# P3DA.net
KiCad netlist of a schematic drawn in EAGLE
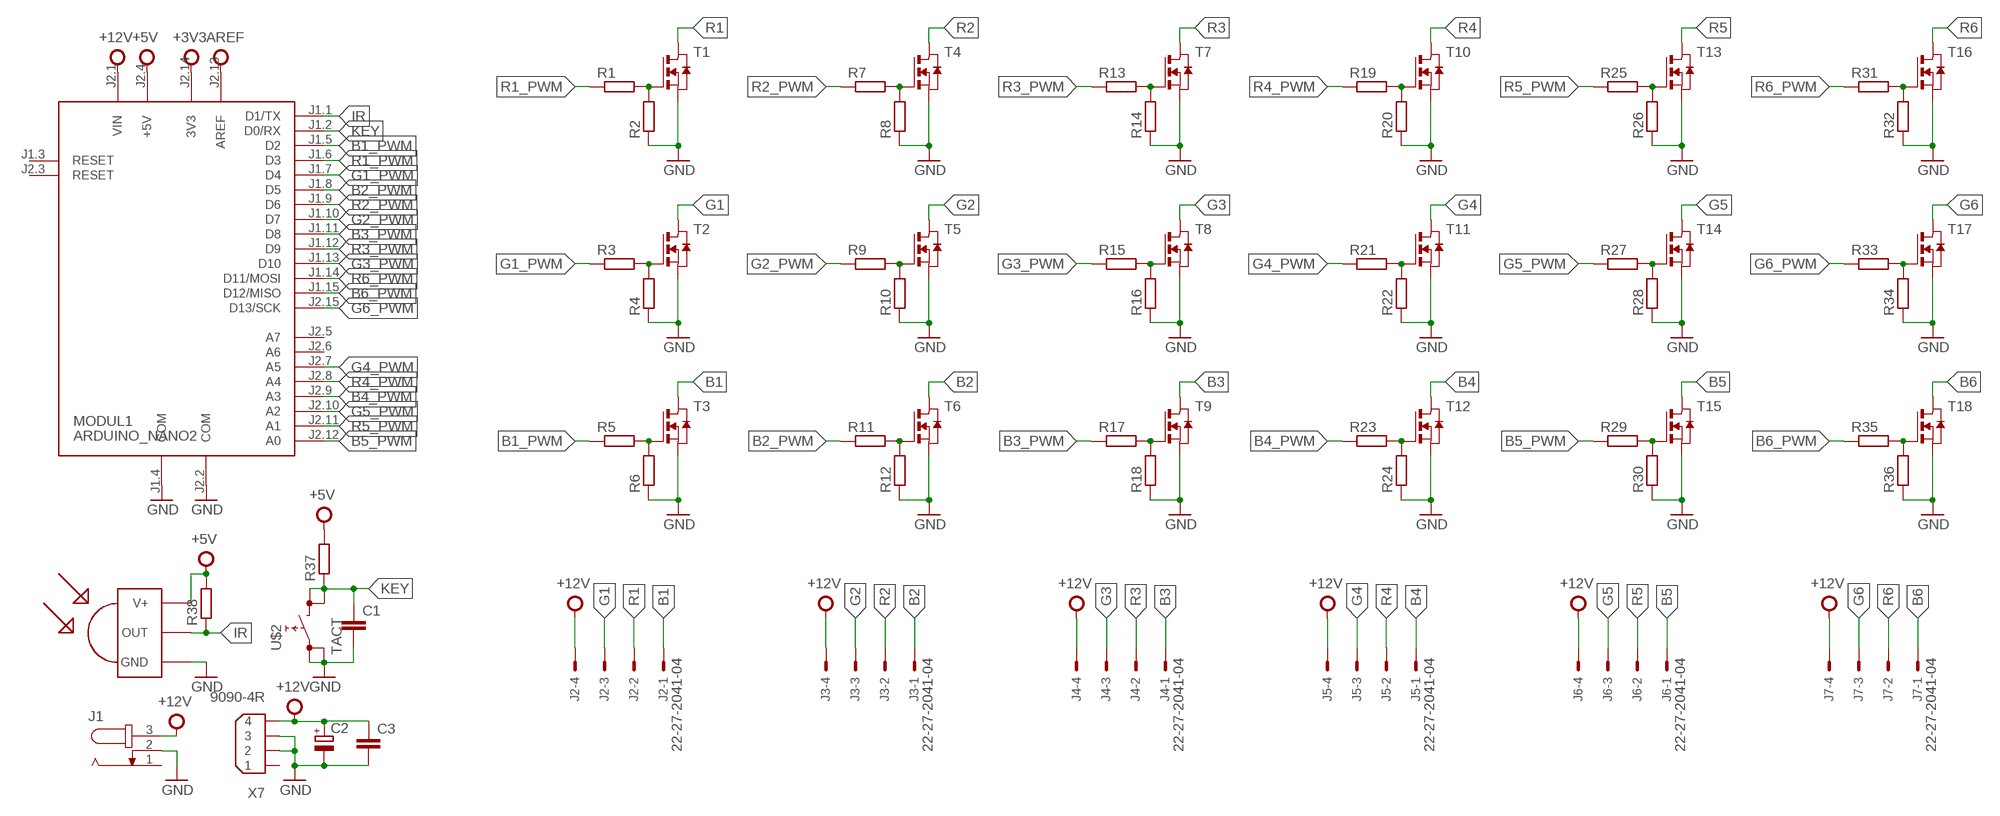
[diagram p0: schematic, sheet 1]

(export (version "E")
  (design (tool "Eeschema 10.0.6"))
  (components
    (comp (ref "C1")
      (value "C-EUC0805")
      (footprint "eagle-import:C0805")
      (libsource (lib "eagle-import") (part "C-EUC0805"))
    )
    (comp (ref "C2")
      (value "CPOL-EUE5-13")
      (footprint "eagle-import:E5-13")
      (libsource (lib "eagle-import") (part "CPOL-EUE5-13"))
    )
    (comp (ref "C3")
      (value "C-EUC1206")
      (footprint "eagle-import:C1206")
      (libsource (lib "eagle-import") (part "C-EUC1206"))
    )
    (comp (ref "J1")
      (value "JACK-PLUG1")
      (footprint "eagle-import:SPC4078")
      (libsource (lib "eagle-import") (part "JACK-PLUG1"))
    )
    (comp (ref "J2")
      (value "22-27-2041-04")
      (footprint "eagle-import:6410-04")
      (libsource (lib "eagle-import") (part "22-?-0427-2041"))
    )
    (comp (ref "J3")
      (value "22-27-2041-04")
      (footprint "eagle-import:6410-04")
      (libsource (lib "eagle-import") (part "22-?-0427-2041"))
    )
    (comp (ref "J4")
      (value "22-27-2041-04")
      (footprint "eagle-import:6410-04")
      (libsource (lib "eagle-import") (part "22-?-0427-2041"))
    )
    (comp (ref "J5")
      (value "22-27-2041-04")
      (footprint "eagle-import:6410-04")
      (libsource (lib "eagle-import") (part "22-?-0427-2041"))
    )
    (comp (ref "J6")
      (value "22-27-2041-04")
      (footprint "eagle-import:6410-04")
      (libsource (lib "eagle-import") (part "22-?-0427-2041"))
    )
    (comp (ref "J7")
      (value "22-27-2041-04")
      (footprint "eagle-import:6410-04")
      (libsource (lib "eagle-import") (part "22-?-0427-2041"))
    )
    (comp (ref "MODUL1")
      (value "ARDUINO_NANO2")
      (footprint "eagle-import:ARDUINO_NANO2")
      (libsource (lib "eagle-import") (part "ARDUINO_NANO2"))
    )
    (comp (ref "R1")
      (value "R-EU_R0805")
      (footprint "eagle-import:R0805")
      (libsource (lib "eagle-import") (part "R-EU_R0805"))
    )
    (comp (ref "R2")
      (value "R-EU_R0805")
      (footprint "eagle-import:R0805")
      (libsource (lib "eagle-import") (part "R-EU_R0805"))
    )
    (comp (ref "R3")
      (value "R-EU_R0805")
      (footprint "eagle-import:R0805")
      (libsource (lib "eagle-import") (part "R-EU_R0805"))
    )
    (comp (ref "R4")
      (value "R-EU_R0805")
      (footprint "eagle-import:R0805")
      (libsource (lib "eagle-import") (part "R-EU_R0805"))
    )
    (comp (ref "R5")
      (value "R-EU_R0805")
      (footprint "eagle-import:R0805")
      (libsource (lib "eagle-import") (part "R-EU_R0805"))
    )
    (comp (ref "R6")
      (value "R-EU_R0805")
      (footprint "eagle-import:R0805")
      (libsource (lib "eagle-import") (part "R-EU_R0805"))
    )
    (comp (ref "R7")
      (value "R-EU_R0805")
      (footprint "eagle-import:R0805")
      (libsource (lib "eagle-import") (part "R-EU_R0805"))
    )
    (comp (ref "R8")
      (value "R-EU_R0805")
      (footprint "eagle-import:R0805")
      (libsource (lib "eagle-import") (part "R-EU_R0805"))
    )
    (comp (ref "R9")
      (value "R-EU_R0805")
      (footprint "eagle-import:R0805")
      (libsource (lib "eagle-import") (part "R-EU_R0805"))
    )
    (comp (ref "R10")
      (value "R-EU_R0805")
      (footprint "eagle-import:R0805")
      (libsource (lib "eagle-import") (part "R-EU_R0805"))
    )
    (comp (ref "R11")
      (value "R-EU_R0805")
      (footprint "eagle-import:R0805")
      (libsource (lib "eagle-import") (part "R-EU_R0805"))
    )
    (comp (ref "R12")
      (value "R-EU_R0805")
      (footprint "eagle-import:R0805")
      (libsource (lib "eagle-import") (part "R-EU_R0805"))
    )
    (comp (ref "R13")
      (value "R-EU_R0805")
      (footprint "eagle-import:R0805")
      (libsource (lib "eagle-import") (part "R-EU_R0805"))
    )
    (comp (ref "R14")
      (value "R-EU_R0805")
      (footprint "eagle-import:R0805")
      (libsource (lib "eagle-import") (part "R-EU_R0805"))
    )
    (comp (ref "R15")
      (value "R-EU_R0805")
      (footprint "eagle-import:R0805")
      (libsource (lib "eagle-import") (part "R-EU_R0805"))
    )
    (comp (ref "R16")
      (value "R-EU_R0805")
      (footprint "eagle-import:R0805")
      (libsource (lib "eagle-import") (part "R-EU_R0805"))
    )
    (comp (ref "R17")
      (value "R-EU_R0805")
      (footprint "eagle-import:R0805")
      (libsource (lib "eagle-import") (part "R-EU_R0805"))
    )
    (comp (ref "R18")
      (value "R-EU_R0805")
      (footprint "eagle-import:R0805")
      (libsource (lib "eagle-import") (part "R-EU_R0805"))
    )
    (comp (ref "R19")
      (value "R-EU_R0805")
      (footprint "eagle-import:R0805")
      (libsource (lib "eagle-import") (part "R-EU_R0805"))
    )
    (comp (ref "R20")
      (value "R-EU_R0805")
      (footprint "eagle-import:R0805")
      (libsource (lib "eagle-import") (part "R-EU_R0805"))
    )
    (comp (ref "R21")
      (value "R-EU_R0805")
      (footprint "eagle-import:R0805")
      (libsource (lib "eagle-import") (part "R-EU_R0805"))
    )
    (comp (ref "R22")
      (value "R-EU_R0805")
      (footprint "eagle-import:R0805")
      (libsource (lib "eagle-import") (part "R-EU_R0805"))
    )
    (comp (ref "R23")
      (value "R-EU_R0805")
      (footprint "eagle-import:R0805")
      (libsource (lib "eagle-import") (part "R-EU_R0805"))
    )
    (comp (ref "R24")
      (value "R-EU_R0805")
      (footprint "eagle-import:R0805")
      (libsource (lib "eagle-import") (part "R-EU_R0805"))
    )
    (comp (ref "R25")
      (value "R-EU_R0805")
      (footprint "eagle-import:R0805")
      (libsource (lib "eagle-import") (part "R-EU_R0805"))
    )
    (comp (ref "R26")
      (value "R-EU_R0805")
      (footprint "eagle-import:R0805")
      (libsource (lib "eagle-import") (part "R-EU_R0805"))
    )
    (comp (ref "R27")
      (value "R-EU_R0805")
      (footprint "eagle-import:R0805")
      (libsource (lib "eagle-import") (part "R-EU_R0805"))
    )
    (comp (ref "R28")
      (value "R-EU_R0805")
      (footprint "eagle-import:R0805")
      (libsource (lib "eagle-import") (part "R-EU_R0805"))
    )
    (comp (ref "R29")
      (value "R-EU_R0805")
      (footprint "eagle-import:R0805")
      (libsource (lib "eagle-import") (part "R-EU_R0805"))
    )
    (comp (ref "R30")
      (value "R-EU_R0805")
      (footprint "eagle-import:R0805")
      (libsource (lib "eagle-import") (part "R-EU_R0805"))
    )
    (comp (ref "R31")
      (value "R-EU_R0805")
      (footprint "eagle-import:R0805")
      (libsource (lib "eagle-import") (part "R-EU_R0805"))
    )
    (comp (ref "R32")
      (value "R-EU_R0805")
      (footprint "eagle-import:R0805")
      (libsource (lib "eagle-import") (part "R-EU_R0805"))
    )
    (comp (ref "R33")
      (value "R-EU_R0805")
      (footprint "eagle-import:R0805")
      (libsource (lib "eagle-import") (part "R-EU_R0805"))
    )
    (comp (ref "R34")
      (value "R-EU_R0805")
      (footprint "eagle-import:R0805")
      (libsource (lib "eagle-import") (part "R-EU_R0805"))
    )
    (comp (ref "R35")
      (value "R-EU_R0805")
      (footprint "eagle-import:R0805")
      (libsource (lib "eagle-import") (part "R-EU_R0805"))
    )
    (comp (ref "R36")
      (value "R-EU_R0805")
      (footprint "eagle-import:R0805")
      (libsource (lib "eagle-import") (part "R-EU_R0805"))
    )
    (comp (ref "R37")
      (value "R-EU_R0805")
      (footprint "eagle-import:R0805")
      (libsource (lib "eagle-import") (part "R-EU_R0805"))
    )
    (comp (ref "R38")
      (value "R-EU_R0805")
      (footprint "eagle-import:R0805")
      (libsource (lib "eagle-import") (part "R-EU_R0805"))
    )
    (comp (ref "T1")
      (value "NMOSSOT23")
      (footprint "eagle-import:SOT-23")
      (libsource (lib "eagle-import") (part "NMOSSOT23"))
    )
    (comp (ref "T2")
      (value "NMOSSOT23")
      (footprint "eagle-import:SOT-23")
      (libsource (lib "eagle-import") (part "NMOSSOT23"))
    )
    (comp (ref "T3")
      (value "NMOSSOT23")
      (footprint "eagle-import:SOT-23")
      (libsource (lib "eagle-import") (part "NMOSSOT23"))
    )
    (comp (ref "T4")
      (value "NMOSSOT23")
      (footprint "eagle-import:SOT-23")
      (libsource (lib "eagle-import") (part "NMOSSOT23"))
    )
    (comp (ref "T5")
      (value "NMOSSOT23")
      (footprint "eagle-import:SOT-23")
      (libsource (lib "eagle-import") (part "NMOSSOT23"))
    )
    (comp (ref "T6")
      (value "NMOSSOT23")
      (footprint "eagle-import:SOT-23")
      (libsource (lib "eagle-import") (part "NMOSSOT23"))
    )
    (comp (ref "T7")
      (value "NMOSSOT23")
      (footprint "eagle-import:SOT-23")
      (libsource (lib "eagle-import") (part "NMOSSOT23"))
    )
    (comp (ref "T8")
      (value "NMOSSOT23")
      (footprint "eagle-import:SOT-23")
      (libsource (lib "eagle-import") (part "NMOSSOT23"))
    )
    (comp (ref "T9")
      (value "NMOSSOT23")
      (footprint "eagle-import:SOT-23")
      (libsource (lib "eagle-import") (part "NMOSSOT23"))
    )
    (comp (ref "T10")
      (value "NMOSSOT23")
      (footprint "eagle-import:SOT-23")
      (libsource (lib "eagle-import") (part "NMOSSOT23"))
    )
    (comp (ref "T11")
      (value "NMOSSOT23")
      (footprint "eagle-import:SOT-23")
      (libsource (lib "eagle-import") (part "NMOSSOT23"))
    )
    (comp (ref "T12")
      (value "NMOSSOT23")
      (footprint "eagle-import:SOT-23")
      (libsource (lib "eagle-import") (part "NMOSSOT23"))
    )
    (comp (ref "T13")
      (value "NMOSSOT23")
      (footprint "eagle-import:SOT-23")
      (libsource (lib "eagle-import") (part "NMOSSOT23"))
    )
    (comp (ref "T14")
      (value "NMOSSOT23")
      (footprint "eagle-import:SOT-23")
      (libsource (lib "eagle-import") (part "NMOSSOT23"))
    )
    (comp (ref "T15")
      (value "NMOSSOT23")
      (footprint "eagle-import:SOT-23")
      (libsource (lib "eagle-import") (part "NMOSSOT23"))
    )
    (comp (ref "T16")
      (value "NMOSSOT23")
      (footprint "eagle-import:SOT-23")
      (libsource (lib "eagle-import") (part "NMOSSOT23"))
    )
    (comp (ref "T17")
      (value "NMOSSOT23")
      (footprint "eagle-import:SOT-23")
      (libsource (lib "eagle-import") (part "NMOSSOT23"))
    )
    (comp (ref "T18")
      (value "NMOSSOT23")
      (footprint "eagle-import:SOT-23")
      (libsource (lib "eagle-import") (part "NMOSSOT23"))
    )
    (comp (ref "U$1")
      (value "TSOP1738")
      (footprint "eagle-import:TSOP17XX")
      (libsource (lib "eagle-import") (part "TSOP1738"))
    )
    (comp (ref "U$2")
      (value "TACT")
      (footprint "eagle-import:TL1105")
      (libsource (lib "eagle-import") (part "TACT"))
    )
    (comp (ref "X7")
      (value "9090-4R")
      (footprint "eagle-import:9090-4R")
      (libsource (lib "eagle-import") (part "9090-4R"))
    )
  )
  (nets
    (net (code "1") (name "+3V3") (class "Default")
      (node (ref "MODUL1") (pin "J2.14") (pinfunction "3V3_J2.14") (pintype "power_in"))
    )
    (net (code "2") (name "+5V") (class "Default")
      (node (ref "MODUL1") (pin "J2.4") (pinfunction "+5V_J2.4") (pintype "power_in"))
      (node (ref "R37") (pin "2") (pinfunction "2_2") (pintype "passive"))
      (node (ref "R38") (pin "2") (pinfunction "2_2") (pintype "passive"))
      (node (ref "U$1") (pin "V+") (pinfunction "V+_V+") (pintype "bidirectional"))
    )
    (net (code "3") (name "+12V") (class "Default")
      (node (ref "C2") (pin "+") (pinfunction "+_+") (pintype "passive"))
      (node (ref "C3") (pin "1") (pinfunction "1_1") (pintype "passive"))
      (node (ref "J1") (pin "3") (pinfunction "3_3") (pintype "passive"))
      (node (ref "J2") (pin "4") (pinfunction "S_4") (pintype "passive"))
      (node (ref "J3") (pin "4") (pinfunction "S_4") (pintype "passive"))
      (node (ref "J4") (pin "4") (pinfunction "S_4") (pintype "passive"))
      (node (ref "J5") (pin "4") (pinfunction "S_4") (pintype "passive"))
      (node (ref "J6") (pin "4") (pinfunction "S_4") (pintype "passive"))
      (node (ref "J7") (pin "4") (pinfunction "S_4") (pintype "passive"))
      (node (ref "MODUL1") (pin "J2.1") (pinfunction "VIN_J2.1") (pintype "power_in"))
      (node (ref "X7") (pin "4") (pinfunction "4_4") (pintype "passive"))
    )
    (net (code "4") (name "AREF") (class "Default")
      (node (ref "MODUL1") (pin "J2.13") (pinfunction "AREF_J2.13") (pintype "power_in"))
    )
    (net (code "5") (name "B1") (class "Default")
      (node (ref "J2") (pin "1") (pinfunction "S_1") (pintype "passive"))
      (node (ref "T3") (pin "1") (pinfunction "D_1") (pintype "passive"))
    )
    (net (code "6") (name "B1_PWM") (class "Default")
      (node (ref "MODUL1") (pin "J1.5") (pinfunction "D2_J1.5") (pintype "bidirectional"))
      (node (ref "R5") (pin "1") (pinfunction "1_1") (pintype "passive"))
    )
    (net (code "7") (name "B2") (class "Default")
      (node (ref "J3") (pin "1") (pinfunction "S_1") (pintype "passive"))
      (node (ref "T6") (pin "1") (pinfunction "D_1") (pintype "passive"))
    )
    (net (code "8") (name "B2_PWM") (class "Default")
      (node (ref "MODUL1") (pin "J1.8") (pinfunction "D5_J1.8") (pintype "bidirectional"))
      (node (ref "R11") (pin "1") (pinfunction "1_1") (pintype "passive"))
    )
    (net (code "9") (name "B3") (class "Default")
      (node (ref "J4") (pin "1") (pinfunction "S_1") (pintype "passive"))
      (node (ref "T9") (pin "1") (pinfunction "D_1") (pintype "passive"))
    )
    (net (code "10") (name "B3_PWM") (class "Default")
      (node (ref "MODUL1") (pin "J1.11") (pinfunction "D8_J1.11") (pintype "bidirectional"))
      (node (ref "R17") (pin "1") (pinfunction "1_1") (pintype "passive"))
    )
    (net (code "11") (name "B4") (class "Default")
      (node (ref "J5") (pin "1") (pinfunction "S_1") (pintype "passive"))
      (node (ref "T12") (pin "1") (pinfunction "D_1") (pintype "passive"))
    )
    (net (code "12") (name "B4_PWM") (class "Default")
      (node (ref "MODUL1") (pin "J2.9") (pinfunction "A3_J2.9") (pintype "bidirectional"))
      (node (ref "R23") (pin "1") (pinfunction "1_1") (pintype "passive"))
    )
    (net (code "13") (name "B5") (class "Default")
      (node (ref "J6") (pin "1") (pinfunction "S_1") (pintype "passive"))
      (node (ref "T15") (pin "1") (pinfunction "D_1") (pintype "passive"))
    )
    (net (code "14") (name "B5_PWM") (class "Default")
      (node (ref "MODUL1") (pin "J2.12") (pinfunction "A0_J2.12") (pintype "bidirectional"))
      (node (ref "R29") (pin "1") (pinfunction "1_1") (pintype "passive"))
    )
    (net (code "15") (name "B6") (class "Default")
      (node (ref "J7") (pin "1") (pinfunction "S_1") (pintype "passive"))
      (node (ref "T18") (pin "1") (pinfunction "D_1") (pintype "passive"))
    )
    (net (code "16") (name "B6_PWM") (class "Default")
      (node (ref "MODUL1") (pin "J1.15") (pinfunction "D12/MISO_J1.15") (pintype "bidirectional"))
      (node (ref "R35") (pin "1") (pinfunction "1_1") (pintype "passive"))
    )
    (net (code "17") (name "G1") (class "Default")
      (node (ref "J2") (pin "3") (pinfunction "S_3") (pintype "passive"))
      (node (ref "T2") (pin "1") (pinfunction "D_1") (pintype "passive"))
    )
    (net (code "18") (name "G1_PWM") (class "Default")
      (node (ref "MODUL1") (pin "J1.7") (pinfunction "D4_J1.7") (pintype "bidirectional"))
      (node (ref "R3") (pin "1") (pinfunction "1_1") (pintype "passive"))
    )
    (net (code "19") (name "G2") (class "Default")
      (node (ref "J3") (pin "3") (pinfunction "S_3") (pintype "passive"))
      (node (ref "T5") (pin "1") (pinfunction "D_1") (pintype "passive"))
    )
    (net (code "20") (name "G2_PWM") (class "Default")
      (node (ref "MODUL1") (pin "J1.10") (pinfunction "D7_J1.10") (pintype "bidirectional"))
      (node (ref "R9") (pin "1") (pinfunction "1_1") (pintype "passive"))
    )
    (net (code "21") (name "G3") (class "Default")
      (node (ref "J4") (pin "3") (pinfunction "S_3") (pintype "passive"))
      (node (ref "T8") (pin "1") (pinfunction "D_1") (pintype "passive"))
    )
    (net (code "22") (name "G3_PWM") (class "Default")
      (node (ref "MODUL1") (pin "J1.13") (pinfunction "D10_J1.13") (pintype "bidirectional"))
      (node (ref "R15") (pin "1") (pinfunction "1_1") (pintype "passive"))
    )
    (net (code "23") (name "G4") (class "Default")
      (node (ref "J5") (pin "3") (pinfunction "S_3") (pintype "passive"))
      (node (ref "T11") (pin "1") (pinfunction "D_1") (pintype "passive"))
    )
    (net (code "24") (name "G4_PWM") (class "Default")
      (node (ref "MODUL1") (pin "J2.7") (pinfunction "A5_J2.7") (pintype "bidirectional"))
      (node (ref "R21") (pin "1") (pinfunction "1_1") (pintype "passive"))
    )
    (net (code "25") (name "G5") (class "Default")
      (node (ref "J6") (pin "3") (pinfunction "S_3") (pintype "passive"))
      (node (ref "T14") (pin "1") (pinfunction "D_1") (pintype "passive"))
    )
    (net (code "26") (name "G5_PWM") (class "Default")
      (node (ref "MODUL1") (pin "J2.10") (pinfunction "A2_J2.10") (pintype "bidirectional"))
      (node (ref "R27") (pin "1") (pinfunction "1_1") (pintype "passive"))
    )
    (net (code "27") (name "G6") (class "Default")
      (node (ref "J7") (pin "3") (pinfunction "S_3") (pintype "passive"))
      (node (ref "T17") (pin "1") (pinfunction "D_1") (pintype "passive"))
    )
    (net (code "28") (name "G6_PWM") (class "Default")
      (node (ref "MODUL1") (pin "J2.15") (pinfunction "D13/SCK_J2.15") (pintype "bidirectional"))
      (node (ref "R33") (pin "1") (pinfunction "1_1") (pintype "passive"))
    )
    (net (code "29") (name "GND") (class "Default")
      (node (ref "C1") (pin "2") (pinfunction "2_2") (pintype "passive"))
      (node (ref "C2") (pin "-") (pinfunction "-_-") (pintype "passive"))
      (node (ref "C3") (pin "2") (pinfunction "2_2") (pintype "passive"))
      (node (ref "J1") (pin "2") (pinfunction "2_2") (pintype "passive"))
      (node (ref "MODUL1") (pin "J1.4") (pinfunction "COM_J1.4") (pintype "power_in"))
      (node (ref "MODUL1") (pin "J2.2") (pinfunction "COM_J2.2") (pintype "power_in"))
      (node (ref "R10") (pin "1") (pinfunction "1_1") (pintype "passive"))
      (node (ref "R12") (pin "1") (pinfunction "1_1") (pintype "passive"))
      (node (ref "R14") (pin "1") (pinfunction "1_1") (pintype "passive"))
      (node (ref "R16") (pin "1") (pinfunction "1_1") (pintype "passive"))
      (node (ref "R18") (pin "1") (pinfunction "1_1") (pintype "passive"))
      (node (ref "R2") (pin "1") (pinfunction "1_1") (pintype "passive"))
      (node (ref "R20") (pin "1") (pinfunction "1_1") (pintype "passive"))
      (node (ref "R22") (pin "1") (pinfunction "1_1") (pintype "passive"))
      (node (ref "R24") (pin "1") (pinfunction "1_1") (pintype "passive"))
      (node (ref "R26") (pin "1") (pinfunction "1_1") (pintype "passive"))
      (node (ref "R28") (pin "1") (pinfunction "1_1") (pintype "passive"))
      (node (ref "R30") (pin "1") (pinfunction "1_1") (pintype "passive"))
      (node (ref "R32") (pin "1") (pinfunction "1_1") (pintype "passive"))
      (node (ref "R34") (pin "1") (pinfunction "1_1") (pintype "passive"))
      (node (ref "R36") (pin "1") (pinfunction "1_1") (pintype "passive"))
      (node (ref "R4") (pin "1") (pinfunction "1_1") (pintype "passive"))
      (node (ref "R6") (pin "1") (pinfunction "1_1") (pintype "passive"))
      (node (ref "R8") (pin "1") (pinfunction "1_1") (pintype "passive"))
      (node (ref "T1") (pin "2") (pinfunction "S_2") (pintype "passive"))
      (node (ref "T10") (pin "2") (pinfunction "S_2") (pintype "passive"))
      (node (ref "T11") (pin "2") (pinfunction "S_2") (pintype "passive"))
      (node (ref "T12") (pin "2") (pinfunction "S_2") (pintype "passive"))
      (node (ref "T13") (pin "2") (pinfunction "S_2") (pintype "passive"))
      (node (ref "T14") (pin "2") (pinfunction "S_2") (pintype "passive"))
      (node (ref "T15") (pin "2") (pinfunction "S_2") (pintype "passive"))
      (node (ref "T16") (pin "2") (pinfunction "S_2") (pintype "passive"))
      (node (ref "T17") (pin "2") (pinfunction "S_2") (pintype "passive"))
      (node (ref "T18") (pin "2") (pinfunction "S_2") (pintype "passive"))
      (node (ref "T2") (pin "2") (pinfunction "S_2") (pintype "passive"))
      (node (ref "T3") (pin "2") (pinfunction "S_2") (pintype "passive"))
      (node (ref "T4") (pin "2") (pinfunction "S_2") (pintype "passive"))
      (node (ref "T5") (pin "2") (pinfunction "S_2") (pintype "passive"))
      (node (ref "T6") (pin "2") (pinfunction "S_2") (pintype "passive"))
      (node (ref "T7") (pin "2") (pinfunction "S_2") (pintype "passive"))
      (node (ref "T8") (pin "2") (pinfunction "S_2") (pintype "passive"))
      (node (ref "T9") (pin "2") (pinfunction "S_2") (pintype "passive"))
      (node (ref "U$1") (pin "GND") (pinfunction "GND_GND") (pintype "bidirectional"))
      (node (ref "U$2") (pin "1") (pinfunction "0_1") (pintype "passive"))
      (node (ref "U$2") (pin "3") (pinfunction "0_3") (pintype "passive"))
      (node (ref "X7") (pin "2") (pinfunction "2_2") (pintype "passive"))
      (node (ref "X7") (pin "3") (pinfunction "3_3") (pintype "passive"))
    )
    (net (code "30") (name "IR") (class "Default")
      (node (ref "MODUL1") (pin "J1.1") (pinfunction "D1/TX_J1.1") (pintype "bidirectional"))
      (node (ref "R38") (pin "1") (pinfunction "1_1") (pintype "passive"))
      (node (ref "U$1") (pin "OUT") (pinfunction "OUT_OUT") (pintype "bidirectional"))
    )
    (net (code "31") (name "KEY") (class "Default")
      (node (ref "C1") (pin "1") (pinfunction "1_1") (pintype "passive"))
      (node (ref "MODUL1") (pin "J1.2") (pinfunction "D0/RX_J1.2") (pintype "bidirectional"))
      (node (ref "R37") (pin "1") (pinfunction "1_1") (pintype "passive"))
      (node (ref "U$2") (pin "2") (pinfunction "1_2") (pintype "passive"))
      (node (ref "U$2") (pin "4") (pinfunction "1_4") (pintype "passive"))
    )
    (net (code "32") (name "Net-(T1-G)") (class "Default")
      (node (ref "R1") (pin "2") (pinfunction "2_2") (pintype "passive"))
      (node (ref "R2") (pin "2") (pinfunction "2_2") (pintype "passive"))
      (node (ref "T1") (pin "3") (pinfunction "G_3") (pintype "passive"))
    )
    (net (code "33") (name "Net-(T2-G)") (class "Default")
      (node (ref "R3") (pin "2") (pinfunction "2_2") (pintype "passive"))
      (node (ref "R4") (pin "2") (pinfunction "2_2") (pintype "passive"))
      (node (ref "T2") (pin "3") (pinfunction "G_3") (pintype "passive"))
    )
    (net (code "34") (name "Net-(T3-G)") (class "Default")
      (node (ref "R5") (pin "2") (pinfunction "2_2") (pintype "passive"))
      (node (ref "R6") (pin "2") (pinfunction "2_2") (pintype "passive"))
      (node (ref "T3") (pin "3") (pinfunction "G_3") (pintype "passive"))
    )
    (net (code "35") (name "Net-(T4-G)") (class "Default")
      (node (ref "R7") (pin "2") (pinfunction "2_2") (pintype "passive"))
      (node (ref "R8") (pin "2") (pinfunction "2_2") (pintype "passive"))
      (node (ref "T4") (pin "3") (pinfunction "G_3") (pintype "passive"))
    )
    (net (code "36") (name "Net-(T5-G)") (class "Default")
      (node (ref "R10") (pin "2") (pinfunction "2_2") (pintype "passive"))
      (node (ref "R9") (pin "2") (pinfunction "2_2") (pintype "passive"))
      (node (ref "T5") (pin "3") (pinfunction "G_3") (pintype "passive"))
    )
    (net (code "37") (name "Net-(T6-G)") (class "Default")
      (node (ref "R11") (pin "2") (pinfunction "2_2") (pintype "passive"))
      (node (ref "R12") (pin "2") (pinfunction "2_2") (pintype "passive"))
      (node (ref "T6") (pin "3") (pinfunction "G_3") (pintype "passive"))
    )
    (net (code "38") (name "Net-(T7-G)") (class "Default")
      (node (ref "R13") (pin "2") (pinfunction "2_2") (pintype "passive"))
      (node (ref "R14") (pin "2") (pinfunction "2_2") (pintype "passive"))
      (node (ref "T7") (pin "3") (pinfunction "G_3") (pintype "passive"))
    )
    (net (code "39") (name "Net-(T8-G)") (class "Default")
      (node (ref "R15") (pin "2") (pinfunction "2_2") (pintype "passive"))
      (node (ref "R16") (pin "2") (pinfunction "2_2") (pintype "passive"))
      (node (ref "T8") (pin "3") (pinfunction "G_3") (pintype "passive"))
    )
    (net (code "40") (name "Net-(T9-G)") (class "Default")
      (node (ref "R17") (pin "2") (pinfunction "2_2") (pintype "passive"))
      (node (ref "R18") (pin "2") (pinfunction "2_2") (pintype "passive"))
      (node (ref "T9") (pin "3") (pinfunction "G_3") (pintype "passive"))
    )
    (net (code "41") (name "Net-(T10-G)") (class "Default")
      (node (ref "R19") (pin "2") (pinfunction "2_2") (pintype "passive"))
      (node (ref "R20") (pin "2") (pinfunction "2_2") (pintype "passive"))
      (node (ref "T10") (pin "3") (pinfunction "G_3") (pintype "passive"))
    )
    (net (code "42") (name "Net-(T11-G)") (class "Default")
      (node (ref "R21") (pin "2") (pinfunction "2_2") (pintype "passive"))
      (node (ref "R22") (pin "2") (pinfunction "2_2") (pintype "passive"))
      (node (ref "T11") (pin "3") (pinfunction "G_3") (pintype "passive"))
    )
    (net (code "43") (name "Net-(T12-G)") (class "Default")
      (node (ref "R23") (pin "2") (pinfunction "2_2") (pintype "passive"))
      (node (ref "R24") (pin "2") (pinfunction "2_2") (pintype "passive"))
      (node (ref "T12") (pin "3") (pinfunction "G_3") (pintype "passive"))
    )
    (net (code "44") (name "Net-(T13-G)") (class "Default")
      (node (ref "R25") (pin "2") (pinfunction "2_2") (pintype "passive"))
      (node (ref "R26") (pin "2") (pinfunction "2_2") (pintype "passive"))
      (node (ref "T13") (pin "3") (pinfunction "G_3") (pintype "passive"))
    )
    (net (code "45") (name "Net-(T14-G)") (class "Default")
      (node (ref "R27") (pin "2") (pinfunction "2_2") (pintype "passive"))
      (node (ref "R28") (pin "2") (pinfunction "2_2") (pintype "passive"))
      (node (ref "T14") (pin "3") (pinfunction "G_3") (pintype "passive"))
    )
    (net (code "46") (name "Net-(T15-G)") (class "Default")
      (node (ref "R29") (pin "2") (pinfunction "2_2") (pintype "passive"))
      (node (ref "R30") (pin "2") (pinfunction "2_2") (pintype "passive"))
      (node (ref "T15") (pin "3") (pinfunction "G_3") (pintype "passive"))
    )
    (net (code "47") (name "Net-(T16-G)") (class "Default")
      (node (ref "R31") (pin "2") (pinfunction "2_2") (pintype "passive"))
      (node (ref "R32") (pin "2") (pinfunction "2_2") (pintype "passive"))
      (node (ref "T16") (pin "3") (pinfunction "G_3") (pintype "passive"))
    )
    (net (code "48") (name "Net-(T17-G)") (class "Default")
      (node (ref "R33") (pin "2") (pinfunction "2_2") (pintype "passive"))
      (node (ref "R34") (pin "2") (pinfunction "2_2") (pintype "passive"))
      (node (ref "T17") (pin "3") (pinfunction "G_3") (pintype "passive"))
    )
    (net (code "49") (name "Net-(T18-G)") (class "Default")
      (node (ref "R35") (pin "2") (pinfunction "2_2") (pintype "passive"))
      (node (ref "R36") (pin "2") (pinfunction "2_2") (pintype "passive"))
      (node (ref "T18") (pin "3") (pinfunction "G_3") (pintype "passive"))
    )
    (net (code "50") (name "R1") (class "Default")
      (node (ref "J2") (pin "2") (pinfunction "S_2") (pintype "passive"))
      (node (ref "T1") (pin "1") (pinfunction "D_1") (pintype "passive"))
    )
    (net (code "51") (name "R1_PWM") (class "Default")
      (node (ref "MODUL1") (pin "J1.6") (pinfunction "D3_J1.6") (pintype "bidirectional"))
      (node (ref "R1") (pin "1") (pinfunction "1_1") (pintype "passive"))
    )
    (net (code "52") (name "R2") (class "Default")
      (node (ref "J3") (pin "2") (pinfunction "S_2") (pintype "passive"))
      (node (ref "T4") (pin "1") (pinfunction "D_1") (pintype "passive"))
    )
    (net (code "53") (name "R2_PWM") (class "Default")
      (node (ref "MODUL1") (pin "J1.9") (pinfunction "D6_J1.9") (pintype "bidirectional"))
      (node (ref "R7") (pin "1") (pinfunction "1_1") (pintype "passive"))
    )
    (net (code "54") (name "R3") (class "Default")
      (node (ref "J4") (pin "2") (pinfunction "S_2") (pintype "passive"))
      (node (ref "T7") (pin "1") (pinfunction "D_1") (pintype "passive"))
    )
    (net (code "55") (name "R3_PWM") (class "Default")
      (node (ref "MODUL1") (pin "J1.12") (pinfunction "D9_J1.12") (pintype "bidirectional"))
      (node (ref "R13") (pin "1") (pinfunction "1_1") (pintype "passive"))
    )
    (net (code "56") (name "R4") (class "Default")
      (node (ref "J5") (pin "2") (pinfunction "S_2") (pintype "passive"))
      (node (ref "T10") (pin "1") (pinfunction "D_1") (pintype "passive"))
    )
    (net (code "57") (name "R4_PWM") (class "Default")
      (node (ref "MODUL1") (pin "J2.8") (pinfunction "A4_J2.8") (pintype "bidirectional"))
      (node (ref "R19") (pin "1") (pinfunction "1_1") (pintype "passive"))
    )
    (net (code "58") (name "R5") (class "Default")
      (node (ref "J6") (pin "2") (pinfunction "S_2") (pintype "passive"))
      (node (ref "T13") (pin "1") (pinfunction "D_1") (pintype "passive"))
    )
    (net (code "59") (name "R5_PWM") (class "Default")
      (node (ref "MODUL1") (pin "J2.11") (pinfunction "A1_J2.11") (pintype "bidirectional"))
      (node (ref "R25") (pin "1") (pinfunction "1_1") (pintype "passive"))
    )
    (net (code "60") (name "R6") (class "Default")
      (node (ref "J7") (pin "2") (pinfunction "S_2") (pintype "passive"))
      (node (ref "T16") (pin "1") (pinfunction "D_1") (pintype "passive"))
    )
    (net (code "61") (name "R6_PWM") (class "Default")
      (node (ref "MODUL1") (pin "J1.14") (pinfunction "D11/MOSI_J1.14") (pintype "bidirectional"))
      (node (ref "R31") (pin "1") (pinfunction "1_1") (pintype "passive"))
    )
    (net (code "62") (name "unconnected-(J1-Pad1)") (class "Default")
      (node (ref "J1") (pin "1") (pinfunction "1_1") (pintype "passive"))
    )
    (net (code "63") (name "unconnected-(MODUL1-A6-PadJ2.6)") (class "Default")
      (node (ref "MODUL1") (pin "J2.6") (pinfunction "A6_J2.6") (pintype "bidirectional"))
    )
    (net (code "64") (name "unconnected-(MODUL1-A7-PadJ2.5)") (class "Default")
      (node (ref "MODUL1") (pin "J2.5") (pinfunction "A7_J2.5") (pintype "bidirectional"))
    )
    (net (code "65") (name "unconnected-(MODUL1-RESET-PadJ1.3)") (class "Default")
      (node (ref "MODUL1") (pin "J1.3") (pinfunction "RESET_J1.3") (pintype "bidirectional"))
    )
    (net (code "66") (name "unconnected-(MODUL1-RESET-PadJ2.3)") (class "Default")
      (node (ref "MODUL1") (pin "J2.3") (pinfunction "RESET_J2.3") (pintype "bidirectional"))
    )
    (net (code "67") (name "unconnected-(X7-Pad1)") (class "Default")
      (node (ref "X7") (pin "1") (pinfunction "1_1") (pintype "passive"))
    )
  )
)
